# 9V_Converter.net
KiCad netlist of a schematic drawn in Altium Designer
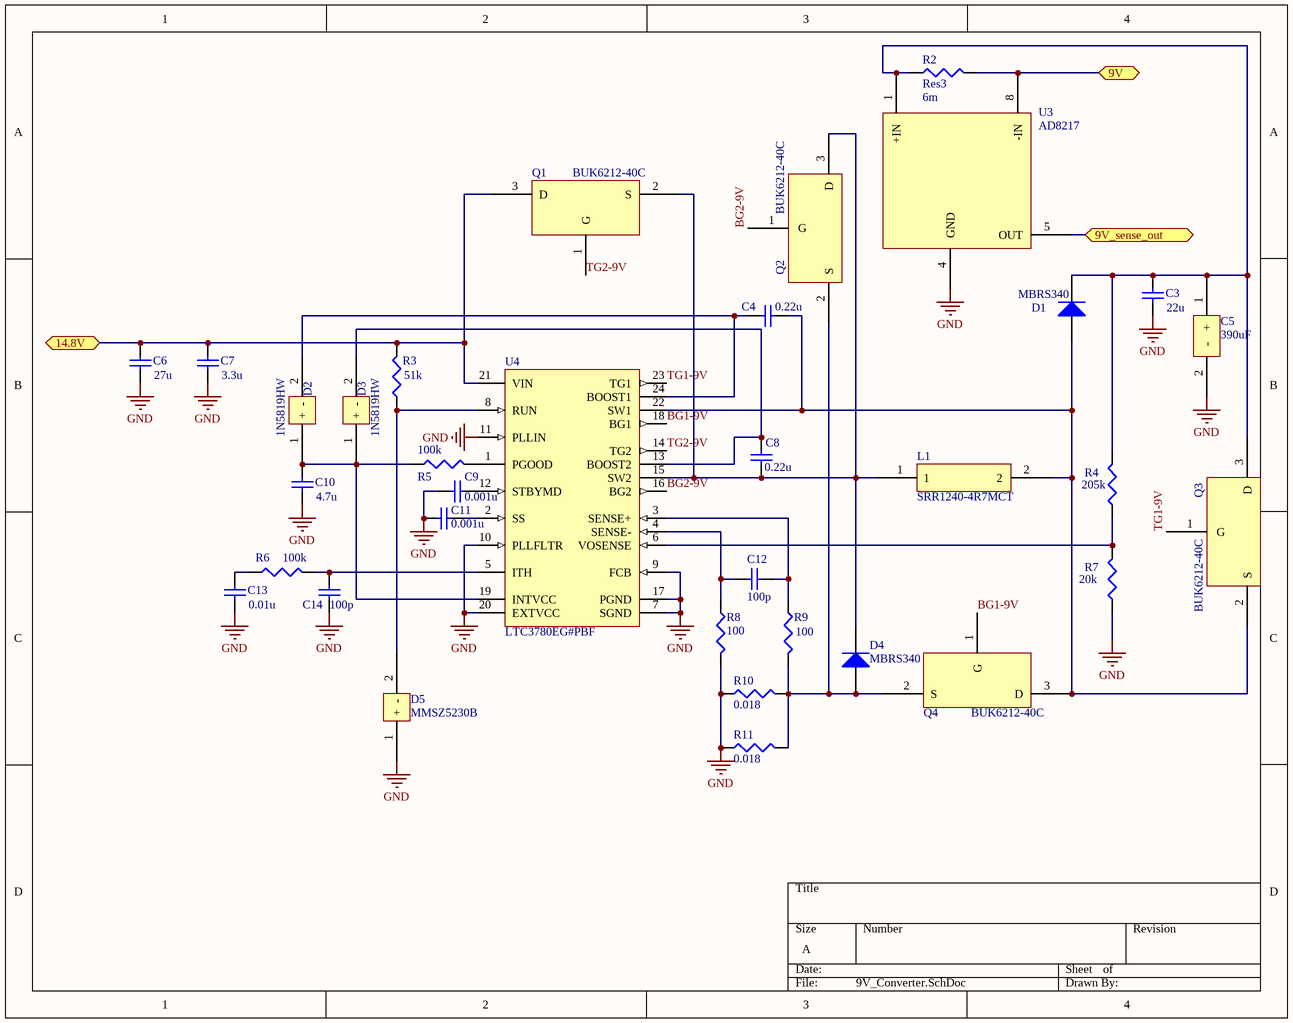
[diagram p0: 9V_Converter.SchDoc]

(export (version "E")
  (design (tool "Eeschema 10.0.6"))
  (components
    (comp (ref "C3")
      (value "22u")
      (footprint "C1206")
      (description "Capacitor (Semiconductor SIM Model)")
      (fields (field (name "Comment") "Cap Semi") (field (name "PUBLISHER") "Altium Limited"))
      (libsource (lib "Miscellaneous Devices") (part "Cap Semi"))
    )
    (comp (ref "C4")
      (value "0.22u")
      (footprint "C1206")
      (description "Capacitor (Semiconductor SIM Model)")
      (fields (field (name "Comment") "Cap Semi") (field (name "PUBLISHER") "Altium Limited"))
      (libsource (lib "Miscellaneous Devices") (part "Cap Semi"))
    )
    (comp (ref "C5")
      (value "390uF")
      (footprint "PCV1E391MCL2GS")
      (description "Aluminum Capacitor")
      (libsource (lib "Integrated_Library") (part "PCV1E391MCL2GS"))
    )
    (comp (ref "C6")
      (value "27u")
      (footprint "C1206")
      (description "Capacitor (Semiconductor SIM Model)")
      (fields (field (name "Comment") "Cap Semi") (field (name "PUBLISHER") "Altium Limited"))
      (libsource (lib "Miscellaneous Devices") (part "Cap Semi"))
    )
    (comp (ref "C7")
      (value "3.3u")
      (footprint "C1206")
      (description "Capacitor (Semiconductor SIM Model)")
      (fields (field (name "Comment") "Cap Semi") (field (name "PUBLISHER") "Altium Limited"))
      (libsource (lib "Miscellaneous Devices") (part "Cap Semi"))
    )
    (comp (ref "C8")
      (value "0.22u")
      (footprint "C1206")
      (description "Capacitor (Semiconductor SIM Model)")
      (fields (field (name "Comment") "Cap Semi") (field (name "PUBLISHER") "Altium Limited"))
      (libsource (lib "Miscellaneous Devices") (part "Cap Semi"))
    )
    (comp (ref "C9")
      (value "0.001u")
      (footprint "C1206")
      (description "Capacitor (Semiconductor SIM Model)")
      (fields (field (name "Comment") "Cap Semi") (field (name "PUBLISHER") "Altium Limited"))
      (libsource (lib "Miscellaneous Devices") (part "Cap Semi"))
    )
    (comp (ref "C10")
      (value "4.7u")
      (footprint "C1206")
      (description "Capacitor (Semiconductor SIM Model)")
      (fields (field (name "Comment") "Cap Semi") (field (name "PUBLISHER") "Altium Limited"))
      (libsource (lib "Miscellaneous Devices") (part "Cap Semi"))
    )
    (comp (ref "C11")
      (value "0.001u")
      (footprint "C1206")
      (description "Capacitor (Semiconductor SIM Model)")
      (fields (field (name "Comment") "Cap Semi") (field (name "PUBLISHER") "Altium Limited"))
      (libsource (lib "Miscellaneous Devices") (part "Cap Semi"))
    )
    (comp (ref "C12")
      (value "100p")
      (footprint "C1206")
      (description "Capacitor (Semiconductor SIM Model)")
      (fields (field (name "Comment") "Cap Semi") (field (name "PUBLISHER") "Altium Limited"))
      (libsource (lib "Miscellaneous Devices") (part "Cap Semi"))
    )
    (comp (ref "C13")
      (value "0.01u")
      (footprint "C1206")
      (description "Capacitor (Semiconductor SIM Model)")
      (fields (field (name "Comment") "Cap Semi") (field (name "PUBLISHER") "Altium Limited"))
      (libsource (lib "Miscellaneous Devices") (part "Cap Semi"))
    )
    (comp (ref "C14")
      (value "100p")
      (footprint "C1206")
      (description "Capacitor (Semiconductor SIM Model)")
      (fields (field (name "Comment") "Cap Semi") (field (name "PUBLISHER") "Altium Limited"))
      (libsource (lib "Miscellaneous Devices") (part "Cap Semi"))
    )
    (comp (ref "D1")
      (value "MBRS340")
      (footprint "SMC")
      (description "Default Diode")
      (fields (field (name "PUBLISHER") "Altium Limited"))
      (libsource (lib "Miscellaneous Devices") (part "Diode"))
    )
    (comp (ref "D2")
      (value "1N5819HW")
      (footprint "1N5819HW")
      (description "1A Schottky Barrier Rectifier")
      (libsource (lib "Integrated_Library") (part "1N5819HW"))
    )
    (comp (ref "D3")
      (value "1N5819HW")
      (footprint "1N5819HW")
      (description "1A Schottky Barrier Rectifier")
      (libsource (lib "Integrated_Library") (part "1N5819HW"))
    )
    (comp (ref "D4")
      (value "MBRS340")
      (footprint "SMC")
      (description "Default Diode")
      (fields (field (name "PUBLISHER") "Altium Limited"))
      (libsource (lib "Miscellaneous Devices") (part "Diode"))
    )
    (comp (ref "D5")
      (value "MMSZ5230B")
      (footprint "MMSZ5230B")
      (description "Zener Diode")
      (libsource (lib "Integrated_Library") (part "MMSZ5230B"))
    )
    (comp (ref "L1")
      (value "SRR1240-4R7MCT")
      (footprint "SRR1240-4R7M")
      (description "Inductor")
      (libsource (lib "Integrated_Library") (part "SRR1240-4R7MCT"))
    )
    (comp (ref "Q1")
      (value "BUK6212-40C")
      (footprint "BUK6212-40C")
      (description "N-Channel TrenchMOS Intermediate Level FET")
      (libsource (lib "") (part "BUK6212-40C_1"))
    )
    (comp (ref "Q2")
      (value "BUK6212-40C")
      (footprint "BUK6212-40C")
      (description "N-Channel TrenchMOS Intermediate Level FET")
      (libsource (lib "Integrated_Library") (part "BUK6212-40C"))
    )
    (comp (ref "Q3")
      (value "BUK6212-40C")
      (footprint "BUK6212-40C")
      (description "N-Channel TrenchMOS Intermediate Level FET")
      (libsource (lib "Integrated_Library") (part "BUK6212-40C"))
    )
    (comp (ref "Q4")
      (value "BUK6212-40C")
      (footprint "BUK6212-40C")
      (description "N-Channel TrenchMOS Intermediate Level FET")
      (libsource (lib "") (part "BUK6212-40C_2"))
    )
    (comp (ref "R2")
      (value "Res3")
      (footprint "14-1210")
      (description "Resistor")
      (fields (field (name "ALTIUM_VALUE") "6m") (field (name "PUBLISHER") "Altium Limited"))
      (libsource (lib "Miscellaneous Devices") (part "Res3"))
    )
    (comp (ref "R3")
      (value "51k")
      (footprint "J1-0603")
      (description "Resistor")
      (fields (field (name "Comment") "Res3") (field (name "PUBLISHER") "Altium Limited"))
      (libsource (lib "Miscellaneous Devices") (part "Res3"))
    )
    (comp (ref "R4")
      (value "205k")
      (footprint "J1-0603")
      (description "Resistor")
      (fields (field (name "Comment") "Res3") (field (name "PUBLISHER") "Altium Limited"))
      (libsource (lib "Miscellaneous Devices") (part "Res3"))
    )
    (comp (ref "R5")
      (value "100k")
      (footprint "J1-0603")
      (description "Resistor")
      (fields (field (name "Comment") "Res3") (field (name "PUBLISHER") "Altium Limited"))
      (libsource (lib "Miscellaneous Devices") (part "Res3"))
    )
    (comp (ref "R6")
      (value "100k")
      (footprint "J1-0603")
      (description "Resistor")
      (fields (field (name "Comment") "Res3") (field (name "PUBLISHER") "Altium Limited"))
      (libsource (lib "Miscellaneous Devices") (part "Res3"))
    )
    (comp (ref "R7")
      (value "20k")
      (footprint "J1-0603")
      (description "Resistor")
      (fields (field (name "Comment") "Res3") (field (name "PUBLISHER") "Altium Limited"))
      (libsource (lib "Miscellaneous Devices") (part "Res3"))
    )
    (comp (ref "R8")
      (value "100")
      (footprint "J1-0603")
      (description "Resistor")
      (fields (field (name "Comment") "Res3") (field (name "PUBLISHER") "Altium Limited"))
      (libsource (lib "Miscellaneous Devices") (part "Res3"))
    )
    (comp (ref "R9")
      (value "100")
      (footprint "J1-0603")
      (description "Resistor")
      (fields (field (name "Comment") "Res3") (field (name "PUBLISHER") "Altium Limited"))
      (libsource (lib "Miscellaneous Devices") (part "Res3"))
    )
    (comp (ref "R10")
      (value "0.018")
      (footprint "J1-0603")
      (description "Resistor")
      (fields (field (name "Comment") "Res3") (field (name "PUBLISHER") "Altium Limited"))
      (libsource (lib "Miscellaneous Devices") (part "Res3"))
    )
    (comp (ref "R11")
      (value "0.018")
      (footprint "J1-0603")
      (description "Resistor")
      (fields (field (name "Comment") "Res3") (field (name "PUBLISHER") "Altium Limited"))
      (libsource (lib "Miscellaneous Devices") (part "Res3"))
    )
    (comp (ref "U3")
      (value "AD8217")
      (footprint "AD8217")
      (description "Current Shunt Moniter")
      (libsource (lib "Integrated_Library") (part "AD8217"))
    )
    (comp (ref "U4")
      (value "LTC3780EG#PBF")
      (footprint "LTC3780 24-Leaqd Plastic SSOP")
      (fields (field (name "MANUFACTURER") "Linear Technology"))
      (libsource (lib "Integrated_Library") (part "LTC3780EG#PBF"))
    )
  )
  (nets
    (net (code "1") (name "/9V") (class "Default")
      (node (ref "R2") (pin "2") (pinfunction "2_2") (pintype "passive"))
      (node (ref "U3") (pin "8") (pinfunction "-IN_8") (pintype "passive"))
    )
    (net (code "2") (name "/9V_sense_out") (class "Default")
      (node (ref "U3") (pin "5") (pinfunction "OUT_5") (pintype "passive"))
    )
    (net (code "3") (name "/14.8V") (class "Default")
      (node (ref "C6") (pin "2") (pinfunction "2_2") (pintype "passive"))
      (node (ref "C7") (pin "2") (pinfunction "2_2") (pintype "passive"))
      (node (ref "Q1") (pin "3") (pinfunction "D_3") (pintype "passive"))
      (node (ref "R3") (pin "2") (pinfunction "2_2") (pintype "passive"))
      (node (ref "U4") (pin "21") (pinfunction "VIN_21") (pintype "power_in"))
    )
    (net (code "4") (name "/BG1-9V") (class "Default")
      (node (ref "Q4") (pin "1") (pinfunction "G_1") (pintype "passive"))
      (node (ref "U4") (pin "18") (pinfunction "BG1_18") (pintype "output"))
    )
    (net (code "5") (name "/BG2-9V") (class "Default")
      (node (ref "Q2") (pin "1") (pinfunction "G_1") (pintype "passive"))
      (node (ref "U4") (pin "16") (pinfunction "BG2_16") (pintype "output"))
    )
    (net (code "6") (name "/TG1-9V") (class "Default")
      (node (ref "Q3") (pin "1") (pinfunction "G_1") (pintype "passive"))
      (node (ref "U4") (pin "23") (pinfunction "TG1_23") (pintype "output"))
    )
    (net (code "7") (name "/TG2-9V") (class "Default")
      (node (ref "Q1") (pin "1") (pinfunction "G_1") (pintype "passive"))
      (node (ref "U4") (pin "14") (pinfunction "TG2_14") (pintype "output"))
    )
    (net (code "8") (name "GND") (class "Default")
      (node (ref "C10") (pin "1") (pinfunction "1_1") (pintype "passive"))
      (node (ref "C11") (pin "1") (pinfunction "1_1") (pintype "passive"))
      (node (ref "C13") (pin "1") (pinfunction "1_1") (pintype "passive"))
      (node (ref "C14") (pin "1") (pinfunction "1_1") (pintype "passive"))
      (node (ref "C3") (pin "1") (pinfunction "1_1") (pintype "passive"))
      (node (ref "C5") (pin "2") (pinfunction "-_2") (pintype "passive"))
      (node (ref "C6") (pin "1") (pinfunction "1_1") (pintype "passive"))
      (node (ref "C7") (pin "1") (pinfunction "1_1") (pintype "passive"))
      (node (ref "C9") (pin "1") (pinfunction "1_1") (pintype "passive"))
      (node (ref "D5") (pin "1") (pinfunction "+_1") (pintype "passive"))
      (node (ref "R10") (pin "1") (pinfunction "1_1") (pintype "passive"))
      (node (ref "R11") (pin "1") (pinfunction "1_1") (pintype "passive"))
      (node (ref "R7") (pin "1") (pinfunction "1_1") (pintype "passive"))
      (node (ref "R8") (pin "2") (pinfunction "2_2") (pintype "passive"))
      (node (ref "U3") (pin "4") (pinfunction "GND_4") (pintype "passive"))
      (node (ref "U4") (pin "10") (pinfunction "PLLFLTR_10") (pintype "input"))
      (node (ref "U4") (pin "11") (pinfunction "PLLIN_11") (pintype "input"))
      (node (ref "U4") (pin "17") (pinfunction "PGND_17") (pintype "power_in"))
      (node (ref "U4") (pin "20") (pinfunction "EXTVCC_20") (pintype "power_in"))
      (node (ref "U4") (pin "7") (pinfunction "SGND_7") (pintype "power_in"))
      (node (ref "U4") (pin "9") (pinfunction "FCB_9") (pintype "input"))
    )
    (net (code "9") (name "Net-(C5-+)") (class "Default")
      (node (ref "C3") (pin "2") (pinfunction "2_2") (pintype "passive"))
      (node (ref "C5") (pin "1") (pinfunction "+_1") (pintype "passive"))
      (node (ref "D1") (pin "2") (pinfunction "K_2") (pintype "passive"))
      (node (ref "Q3") (pin "3") (pinfunction "D_3") (pintype "passive"))
      (node (ref "R2") (pin "1") (pinfunction "1_1") (pintype "passive"))
      (node (ref "R4") (pin "2") (pinfunction "2_2") (pintype "passive"))
      (node (ref "U3") (pin "1") (pinfunction "+IN_1") (pintype "passive"))
    )
    (net (code "10") (name "Net-(C13-Pad2)") (class "Default")
      (node (ref "C13") (pin "2") (pinfunction "2_2") (pintype "passive"))
      (node (ref "R6") (pin "1") (pinfunction "1_1") (pintype "passive"))
    )
    (net (code "11") (name "Net-(D1-A)") (class "Default")
      (node (ref "C4") (pin "1") (pinfunction "1_1") (pintype "passive"))
      (node (ref "D1") (pin "1") (pinfunction "A_1") (pintype "passive"))
      (node (ref "L1") (pin "2") (pinfunction "2_2") (pintype "passive"))
      (node (ref "Q3") (pin "2") (pinfunction "S_2") (pintype "passive"))
      (node (ref "Q4") (pin "3") (pinfunction "D_3") (pintype "passive"))
      (node (ref "U4") (pin "22") (pinfunction "SW1_22") (pintype "passive"))
    )
    (net (code "12") (name "Net-(D2-+)") (class "Default")
      (node (ref "C10") (pin "2") (pinfunction "2_2") (pintype "passive"))
      (node (ref "D2") (pin "1") (pinfunction "+_1") (pintype "passive"))
      (node (ref "D3") (pin "1") (pinfunction "+_1") (pintype "passive"))
      (node (ref "R5") (pin "1") (pinfunction "1_1") (pintype "passive"))
      (node (ref "U4") (pin "19") (pinfunction "INTVCC_19") (pintype "power_in"))
    )
    (net (code "13") (name "Net-(D2--)") (class "Default")
      (node (ref "C4") (pin "2") (pinfunction "2_2") (pintype "passive"))
      (node (ref "D2") (pin "2") (pinfunction "-_2") (pintype "passive"))
      (node (ref "U4") (pin "24") (pinfunction "BOOST1_24") (pintype "passive"))
    )
    (net (code "14") (name "Net-(D3--)") (class "Default")
      (node (ref "C8") (pin "2") (pinfunction "2_2") (pintype "passive"))
      (node (ref "D3") (pin "2") (pinfunction "-_2") (pintype "passive"))
      (node (ref "U4") (pin "13") (pinfunction "BOOST2_13") (pintype "passive"))
    )
    (net (code "15") (name "Net-(D4-A)") (class "Default")
      (node (ref "D4") (pin "1") (pinfunction "A_1") (pintype "passive"))
      (node (ref "Q2") (pin "2") (pinfunction "S_2") (pintype "passive"))
      (node (ref "Q4") (pin "2") (pinfunction "S_2") (pintype "passive"))
      (node (ref "R10") (pin "2") (pinfunction "2_2") (pintype "passive"))
      (node (ref "R11") (pin "2") (pinfunction "2_2") (pintype "passive"))
      (node (ref "R9") (pin "2") (pinfunction "2_2") (pintype "passive"))
    )
    (net (code "16") (name "Net-(D4-K)") (class "Default")
      (node (ref "C8") (pin "1") (pinfunction "1_1") (pintype "passive"))
      (node (ref "D4") (pin "2") (pinfunction "K_2") (pintype "passive"))
      (node (ref "L1") (pin "1") (pinfunction "1_1") (pintype "passive"))
      (node (ref "Q1") (pin "2") (pinfunction "S_2") (pintype "passive"))
      (node (ref "Q2") (pin "3") (pinfunction "D_3") (pintype "passive"))
      (node (ref "U4") (pin "15") (pinfunction "SW2_15") (pintype "passive"))
    )
    (net (code "17") (name "Net-(D5--)") (class "Default")
      (node (ref "D5") (pin "2") (pinfunction "-_2") (pintype "passive"))
      (node (ref "R3") (pin "1") (pinfunction "1_1") (pintype "passive"))
      (node (ref "U4") (pin "8") (pinfunction "RUN_8") (pintype "input"))
    )
    (net (code "18") (name "Net-(U4-ITH)") (class "Default")
      (node (ref "C14") (pin "2") (pinfunction "2_2") (pintype "passive"))
      (node (ref "R6") (pin "2") (pinfunction "2_2") (pintype "passive"))
      (node (ref "U4") (pin "5") (pinfunction "ITH_5") (pintype "passive"))
    )
    (net (code "19") (name "Net-(U4-PGOOD)") (class "Default")
      (node (ref "R5") (pin "2") (pinfunction "2_2") (pintype "passive"))
      (node (ref "U4") (pin "1") (pinfunction "PGOOD_1") (pintype "open_collector"))
    )
    (net (code "20") (name "Net-(U4-SENSE+)") (class "Default")
      (node (ref "C12") (pin "2") (pinfunction "2_2") (pintype "passive"))
      (node (ref "R9") (pin "1") (pinfunction "1_1") (pintype "passive"))
      (node (ref "U4") (pin "3") (pinfunction "SENSE+_3") (pintype "input"))
    )
    (net (code "21") (name "Net-(U4-SENSE-)") (class "Default")
      (node (ref "C12") (pin "1") (pinfunction "1_1") (pintype "passive"))
      (node (ref "R8") (pin "1") (pinfunction "1_1") (pintype "passive"))
      (node (ref "U4") (pin "4") (pinfunction "SENSE-_4") (pintype "input"))
    )
    (net (code "22") (name "Net-(U4-SS)") (class "Default")
      (node (ref "C11") (pin "2") (pinfunction "2_2") (pintype "passive"))
      (node (ref "U4") (pin "2") (pinfunction "SS_2") (pintype "input"))
    )
    (net (code "23") (name "Net-(U4-STBYMD)") (class "Default")
      (node (ref "C9") (pin "2") (pinfunction "2_2") (pintype "passive"))
      (node (ref "U4") (pin "12") (pinfunction "STBYMD_12") (pintype "input"))
    )
    (net (code "24") (name "Net-(U4-VOSENSE)") (class "Default")
      (node (ref "R4") (pin "1") (pinfunction "1_1") (pintype "passive"))
      (node (ref "R7") (pin "2") (pinfunction "2_2") (pintype "passive"))
      (node (ref "U4") (pin "6") (pinfunction "VOSENSE_6") (pintype "input"))
    )
  )
)
